# ForceACQ.net
KiCad netlist of a schematic drawn in Altium Designer
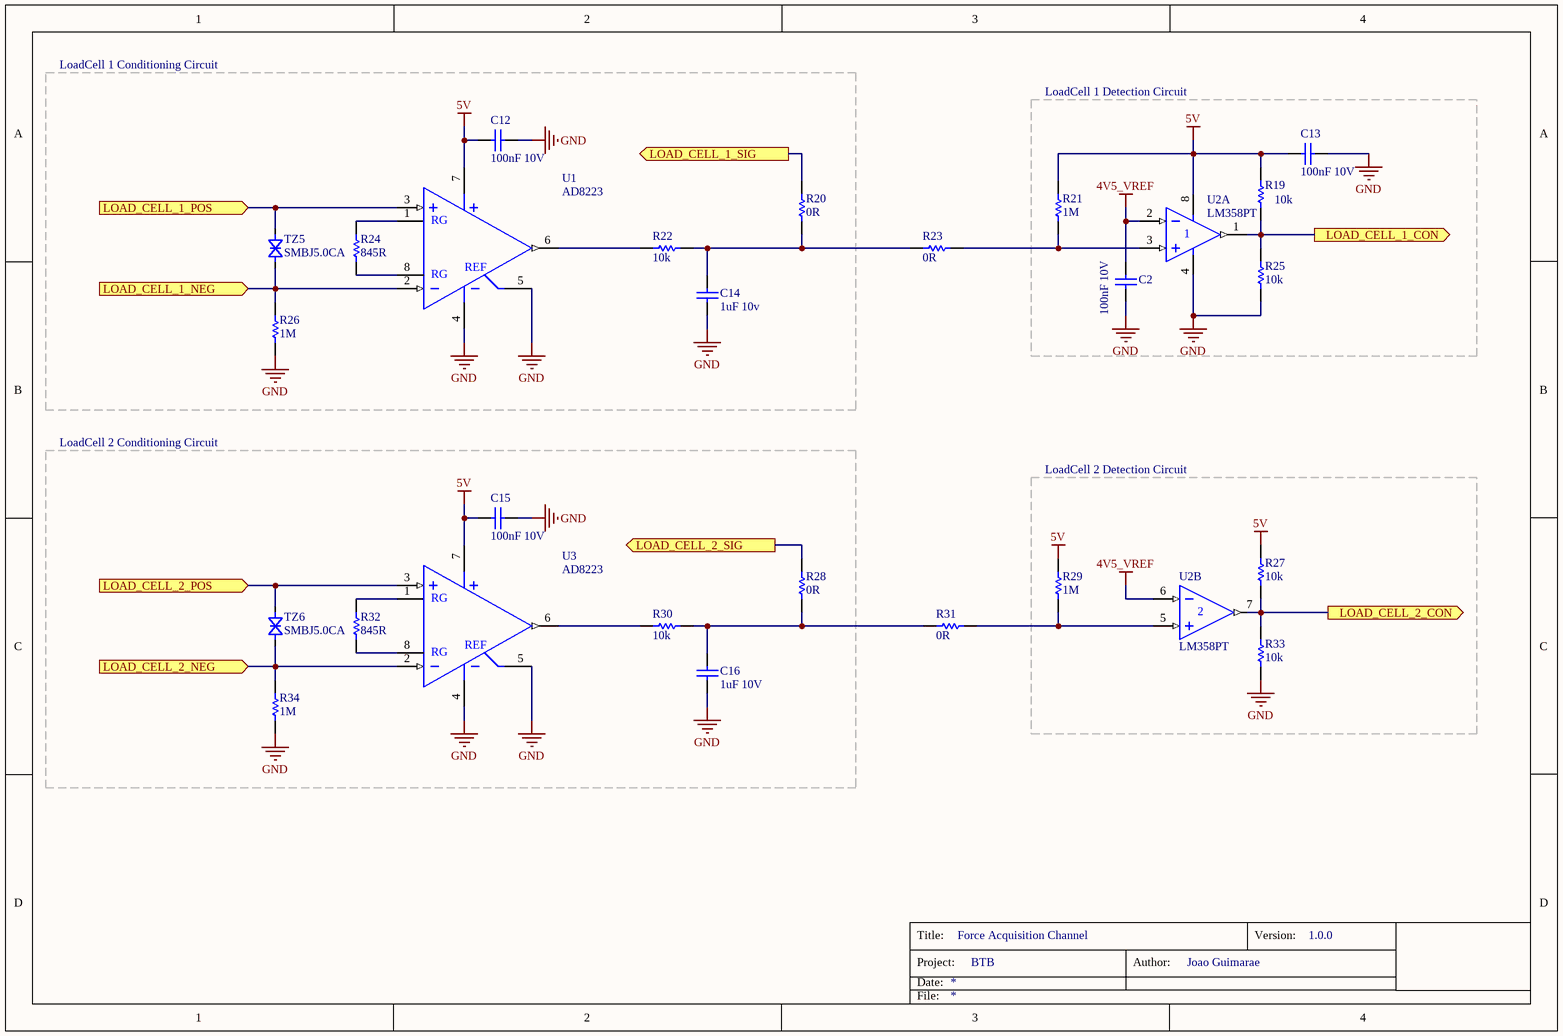
[diagram p0: ForceACQ.SchDoc]

(export (version "E")
  (design (tool "Eeschema 10.0.6"))
  (components
    (comp (ref "C2")
      (value "100nF 10V")
      (footprint "0402")
      (description "Capacitor")
      (fields (field (name "PARTNUMBER") "CAP.100n.10V.20%.SMD.0402") (field (name "MANUFACTURER") "Wurth"))
      (libsource (lib "IntLib") (part "Cap"))
    )
    (comp (ref "C12")
      (value "100nF 10V")
      (footprint "0402")
      (description "Capacitor")
      (fields (field (name "PARTNUMBER") "CAP.100n.10V.20%.SMD.0402") (field (name "MANUFACTURER") "Wurth"))
      (libsource (lib "IntLib") (part "Cap"))
    )
    (comp (ref "C13")
      (value "100nF 10V")
      (footprint "0402")
      (description "Capacitor")
      (fields (field (name "PARTNUMBER") "CAP.100n.10V.20%.SMD.0402") (field (name "MANUFACTURER") "Wurth"))
      (libsource (lib "IntLib") (part "Cap"))
    )
    (comp (ref "C14")
      (value "1uF 10v")
      (footprint "C0805")
      (description "Capacitor")
      (fields (field (name "PARTNUMBER") "CAP.1u.10V.10%.SMD.0805") (field (name "MANUFACTURER") "Vishay"))
      (libsource (lib "IntLib") (part "Cap"))
    )
    (comp (ref "C15")
      (value "100nF 10V")
      (footprint "0402")
      (description "Capacitor")
      (fields (field (name "PARTNUMBER") "CAP.100n.10V.20%.SMD.0402") (field (name "MANUFACTURER") "Wurth"))
      (libsource (lib "IntLib") (part "Cap"))
    )
    (comp (ref "C16")
      (value "1uF 10V")
      (footprint "C0805")
      (description "Capacitor")
      (fields (field (name "PARTNUMBER") "CAP.1u.10V.10%.SMD.0805") (field (name "MANUFACTURER") "Vishay"))
      (libsource (lib "IntLib") (part "Cap"))
    )
    (comp (ref "R19")
      (value "10k")
      (footprint "6-0805_M")
      (description "Resistor")
      (fields (field (name "PARTNUMBER") "RES.10K.1/8W.5%.SMD.0805") (field (name "MANUFACTURER") "Yageo"))
      (libsource (lib "IntLib") (part "Res"))
    )
    (comp (ref "R20")
      (value "0R")
      (footprint "6-0805_M")
      (description "Resistor")
      (fields (field (name "PARTNUMBER") "RES.0R.1/8W.5%.SMD.0805") (field (name "MANUFACTURER") "Vishay"))
      (libsource (lib "IntLib") (part "Res"))
    )
    (comp (ref "R21")
      (value "1M")
      (footprint "6-0805_M")
      (description "Resistor")
      (fields (field (name "PARTNUMBER") "RES.1M.1/8W.5%.SMD.0805") (field (name "MANUFACTURER") "Bourns"))
      (libsource (lib "IntLib") (part "Res"))
    )
    (comp (ref "R22")
      (value "10k")
      (footprint "6-0805_M")
      (description "Resistor")
      (fields (field (name "PARTNUMBER") "RES.10K.1/8W.5%.SMD.0805") (field (name "MANUFACTURER") "Yageo"))
      (libsource (lib "IntLib") (part "Res"))
    )
    (comp (ref "R23")
      (value "0R")
      (footprint "6-0805_M")
      (description "Resistor")
      (fields (field (name "PARTNUMBER") "RES.0R.1/8W.5%.SMD.0805") (field (name "MANUFACTURER") "Vishay"))
      (libsource (lib "IntLib") (part "Res"))
    )
    (comp (ref "R24")
      (value "845R")
      (footprint "0402")
      (description "Resistor")
      (fields (field (name "PARTNUMBER") "RES.845R.1/8W.1%.SMD.0402") (field (name "MANUFACTURER") "Yageo"))
      (libsource (lib "IntLib") (part "Res"))
    )
    (comp (ref "R25")
      (value "10k")
      (footprint "6-0805_M")
      (description "Resistor")
      (fields (field (name "PARTNUMBER") "RES.10K.1/8W.5%.SMD.0805") (field (name "MANUFACTURER") "Yageo"))
      (libsource (lib "IntLib") (part "Res"))
    )
    (comp (ref "R26")
      (value "1M")
      (footprint "6-0805_M")
      (description "Resistor")
      (fields (field (name "PARTNUMBER") "RES.1M.1/8W.5%.SMD.0805") (field (name "MANUFACTURER") "Bourns"))
      (libsource (lib "IntLib") (part "Res"))
    )
    (comp (ref "R27")
      (value "10k")
      (footprint "6-0805_M")
      (description "Resistor")
      (fields (field (name "PARTNUMBER") "RES.10K.1/8W.5%.SMD.0805") (field (name "MANUFACTURER") "Yageo"))
      (libsource (lib "IntLib") (part "Res"))
    )
    (comp (ref "R28")
      (value "0R")
      (footprint "6-0805_M")
      (description "Resistor")
      (fields (field (name "PARTNUMBER") "RES.0R.1/8W.5%.SMD.0805") (field (name "MANUFACTURER") "Vishay"))
      (libsource (lib "IntLib") (part "Res"))
    )
    (comp (ref "R29")
      (value "1M")
      (footprint "6-0805_M")
      (description "Resistor")
      (fields (field (name "PARTNUMBER") "RES.1M.1/8W.5%.SMD.0805") (field (name "MANUFACTURER") "Bourns"))
      (libsource (lib "IntLib") (part "Res"))
    )
    (comp (ref "R30")
      (value "10k")
      (footprint "6-0805_M")
      (description "Resistor")
      (fields (field (name "PARTNUMBER") "RES.10K.1/8W.5%.SMD.0805") (field (name "MANUFACTURER") "Yageo"))
      (libsource (lib "IntLib") (part "Res"))
    )
    (comp (ref "R31")
      (value "0R")
      (footprint "6-0805_M")
      (description "Resistor")
      (fields (field (name "PARTNUMBER") "RES.0R.1/8W.5%.SMD.0805") (field (name "MANUFACTURER") "Vishay"))
      (libsource (lib "IntLib") (part "Res"))
    )
    (comp (ref "R32")
      (value "845R")
      (footprint "0402")
      (description "Resistor")
      (fields (field (name "PARTNUMBER") "RES.845R.1/8W.1%.SMD.0402") (field (name "MANUFACTURER") "Yageo"))
      (libsource (lib "IntLib") (part "Res"))
    )
    (comp (ref "R33")
      (value "10k")
      (footprint "6-0805_M")
      (description "Resistor")
      (fields (field (name "PARTNUMBER") "RES.10K.1/8W.5%.SMD.0805") (field (name "MANUFACTURER") "Yageo"))
      (libsource (lib "IntLib") (part "Res"))
    )
    (comp (ref "R34")
      (value "1M")
      (footprint "6-0805_M")
      (description "Resistor")
      (fields (field (name "PARTNUMBER") "RES.1M.1/8W.5%.SMD.0805") (field (name "MANUFACTURER") "Bourns"))
      (libsource (lib "IntLib") (part "Res"))
    )
    (comp (ref "TZ5")
      (value "SMBJ5.0CA")
      (footprint "DO-214AA")
      (description "ESD Suppressors / TVS Diodes 5Vr 600W 65.3A 5% BiDirectional")
      (fields (field (name "MANUFACTURER") "Bourns"))
      (libsource (lib "IntLib") (part "SMBJ5.0CA"))
    )
    (comp (ref "TZ6")
      (value "SMBJ5.0CA")
      (footprint "DO-214AA")
      (description "ESD Suppressors / TVS Diodes 5Vr 600W 65.3A 5% BiDirectional")
      (fields (field (name "MANUFACTURER") "Bourns"))
      (libsource (lib "IntLib") (part "SMBJ5.0CA"))
    )
    (comp (ref "U1")
      (value "AD8223")
      (footprint "SO8_M")
      (description "Precision Instrumentation Amplifier")
      (fields (field (name "PARTNUMBER") "AD8223ARZ") (field (name "MANUFACTURER") "Analog Devices"))
      (libsource (lib "IntLib") (part "AD8223"))
    )
    (comp (ref "U2")
      (value "LM358PT")
      (footprint "TSOP-8")
      (description "Operational Amplifiers - Op Amps Dual Low Power")
      (fields (field (name "MANUFACTURER") "STMicroelectronics"))
      (libsource (lib "IntLib") (part "LM358PT"))
    )
    (comp (ref "U3")
      (value "AD8223")
      (footprint "SO8_M")
      (description "Precision Instrumentation Amplifier")
      (fields (field (name "PARTNUMBER") "AD8223ARZ") (field (name "MANUFACTURER") "Analog Devices"))
      (libsource (lib "IntLib") (part "AD8223"))
    )
  )
  (nets
    (net (code "1") (name "/LOAD_CELL_1_CON") (class "Default")
      (node (ref "R19") (pin "2") (pinfunction "2_2") (pintype "passive"))
      (node (ref "R25") (pin "1") (pinfunction "1_1") (pintype "passive"))
      (node (ref "U2") (pin "1") (pinfunction "OUT_1") (pintype "output"))
    )
    (net (code "2") (name "/LOAD_CELL_1_NEG") (class "Default")
      (node (ref "R26") (pin "1") (pinfunction "1_1") (pintype "passive"))
      (node (ref "TZ5") (pin "1") (pinfunction "C_1") (pintype "passive"))
      (node (ref "U1") (pin "2") (pinfunction "IN-_2") (pintype "input"))
    )
    (net (code "3") (name "/LOAD_CELL_1_POS") (class "Default")
      (node (ref "TZ5") (pin "2") (pinfunction "A_2") (pintype "passive"))
      (node (ref "U1") (pin "3") (pinfunction "IN+_3") (pintype "input"))
    )
    (net (code "4") (name "/LOAD_CELL_1_SIG") (class "Default")
      (node (ref "R20") (pin "2") (pinfunction "2_2") (pintype "passive"))
    )
    (net (code "5") (name "/LOAD_CELL_2_CON") (class "Default")
      (node (ref "R27") (pin "2") (pinfunction "2_2") (pintype "passive"))
      (node (ref "R33") (pin "1") (pinfunction "1_1") (pintype "passive"))
      (node (ref "U2") (pin "7") (pinfunction "OUT_7") (pintype "output"))
    )
    (net (code "6") (name "/LOAD_CELL_2_NEG") (class "Default")
      (node (ref "R34") (pin "1") (pinfunction "1_1") (pintype "passive"))
      (node (ref "TZ6") (pin "1") (pinfunction "C_1") (pintype "passive"))
      (node (ref "U3") (pin "2") (pinfunction "IN-_2") (pintype "input"))
    )
    (net (code "7") (name "/LOAD_CELL_2_POS") (class "Default")
      (node (ref "TZ6") (pin "2") (pinfunction "A_2") (pintype "passive"))
      (node (ref "U3") (pin "3") (pinfunction "IN+_3") (pintype "input"))
    )
    (net (code "8") (name "/LOAD_CELL_2_SIG") (class "Default")
      (node (ref "R28") (pin "2") (pinfunction "2_2") (pintype "passive"))
    )
    (net (code "9") (name "4V5_VREF") (class "Default")
      (node (ref "C2") (pin "2") (pinfunction "2_2") (pintype "passive"))
      (node (ref "U2") (pin "2") (pinfunction "IN-_2") (pintype "input"))
      (node (ref "U2") (pin "6") (pinfunction "IN-_6") (pintype "input"))
    )
    (net (code "10") (name "5V") (class "Default")
      (node (ref "C12") (pin "1") (pinfunction "1_1") (pintype "passive"))
      (node (ref "C13") (pin "2") (pinfunction "2_2") (pintype "passive"))
      (node (ref "C15") (pin "1") (pinfunction "1_1") (pintype "passive"))
      (node (ref "R19") (pin "1") (pinfunction "1_1") (pintype "passive"))
      (node (ref "R21") (pin "1") (pinfunction "1_1") (pintype "passive"))
      (node (ref "R27") (pin "1") (pinfunction "1_1") (pintype "passive"))
      (node (ref "R29") (pin "1") (pinfunction "1_1") (pintype "passive"))
      (node (ref "U1") (pin "7") (pinfunction "+Vs_7") (pintype "power_in"))
      (node (ref "U2") (pin "8") (pinfunction "Vs+_8") (pintype "passive"))
      (node (ref "U3") (pin "7") (pinfunction "+Vs_7") (pintype "power_in"))
    )
    (net (code "11") (name "GND") (class "Default")
      (node (ref "C12") (pin "2") (pinfunction "2_2") (pintype "passive"))
      (node (ref "C13") (pin "1") (pinfunction "1_1") (pintype "passive"))
      (node (ref "C14") (pin "1") (pinfunction "1_1") (pintype "passive"))
      (node (ref "C15") (pin "2") (pinfunction "2_2") (pintype "passive"))
      (node (ref "C16") (pin "1") (pinfunction "1_1") (pintype "passive"))
      (node (ref "C2") (pin "1") (pinfunction "1_1") (pintype "passive"))
      (node (ref "R25") (pin "2") (pinfunction "2_2") (pintype "passive"))
      (node (ref "R26") (pin "2") (pinfunction "2_2") (pintype "passive"))
      (node (ref "R33") (pin "2") (pinfunction "2_2") (pintype "passive"))
      (node (ref "R34") (pin "2") (pinfunction "2_2") (pintype "passive"))
      (node (ref "U1") (pin "4") (pinfunction "-Vs_4") (pintype "power_in"))
      (node (ref "U1") (pin "5") (pinfunction "REF_5") (pintype "passive"))
      (node (ref "U2") (pin "4") (pinfunction "Vs-_4") (pintype "passive"))
      (node (ref "U3") (pin "4") (pinfunction "-Vs_4") (pintype "power_in"))
      (node (ref "U3") (pin "5") (pinfunction "REF_5") (pintype "passive"))
    )
    (net (code "12") (name "Net-(C14-Pad2)") (class "Default")
      (node (ref "C14") (pin "2") (pinfunction "2_2") (pintype "passive"))
      (node (ref "R20") (pin "1") (pinfunction "1_1") (pintype "passive"))
      (node (ref "R22") (pin "2") (pinfunction "2_2") (pintype "passive"))
      (node (ref "R23") (pin "2") (pinfunction "2_2") (pintype "passive"))
    )
    (net (code "13") (name "Net-(C16-Pad2)") (class "Default")
      (node (ref "C16") (pin "2") (pinfunction "2_2") (pintype "passive"))
      (node (ref "R28") (pin "1") (pinfunction "1_1") (pintype "passive"))
      (node (ref "R30") (pin "2") (pinfunction "2_2") (pintype "passive"))
      (node (ref "R31") (pin "2") (pinfunction "2_2") (pintype "passive"))
    )
    (net (code "14") (name "Net-(R24-Pad1)") (class "Default")
      (node (ref "R24") (pin "1") (pinfunction "1_1") (pintype "passive"))
      (node (ref "U1") (pin "8") (pinfunction "RG_8") (pintype "passive"))
    )
    (net (code "15") (name "Net-(R24-Pad2)") (class "Default")
      (node (ref "R24") (pin "2") (pinfunction "2_2") (pintype "passive"))
      (node (ref "U1") (pin "1") (pinfunction "RG_1") (pintype "passive"))
    )
    (net (code "16") (name "Net-(R32-Pad1)") (class "Default")
      (node (ref "R32") (pin "1") (pinfunction "1_1") (pintype "passive"))
      (node (ref "U3") (pin "8") (pinfunction "RG_8") (pintype "passive"))
    )
    (net (code "17") (name "Net-(R32-Pad2)") (class "Default")
      (node (ref "R32") (pin "2") (pinfunction "2_2") (pintype "passive"))
      (node (ref "U3") (pin "1") (pinfunction "RG_1") (pintype "passive"))
    )
    (net (code "18") (name "Net-(U1-OUT)") (class "Default")
      (node (ref "R22") (pin "1") (pinfunction "1_1") (pintype "passive"))
      (node (ref "U1") (pin "6") (pinfunction "OUT_6") (pintype "output"))
    )
    (net (code "19") (name "Net-(U2A-IN+)") (class "Default")
      (node (ref "R21") (pin "2") (pinfunction "2_2") (pintype "passive"))
      (node (ref "R23") (pin "1") (pinfunction "1_1") (pintype "passive"))
      (node (ref "U2") (pin "3") (pinfunction "IN+_3") (pintype "input"))
    )
    (net (code "20") (name "Net-(U2B-IN+)") (class "Default")
      (node (ref "R29") (pin "2") (pinfunction "2_2") (pintype "passive"))
      (node (ref "R31") (pin "1") (pinfunction "1_1") (pintype "passive"))
      (node (ref "U2") (pin "5") (pinfunction "IN+_5") (pintype "input"))
    )
    (net (code "21") (name "Net-(U3-OUT)") (class "Default")
      (node (ref "R30") (pin "1") (pinfunction "1_1") (pintype "passive"))
      (node (ref "U3") (pin "6") (pinfunction "OUT_6") (pintype "output"))
    )
  )
)
